# WireLessPhone_Amp.net
KiCad netlist of a schematic drawn in Altium Designer
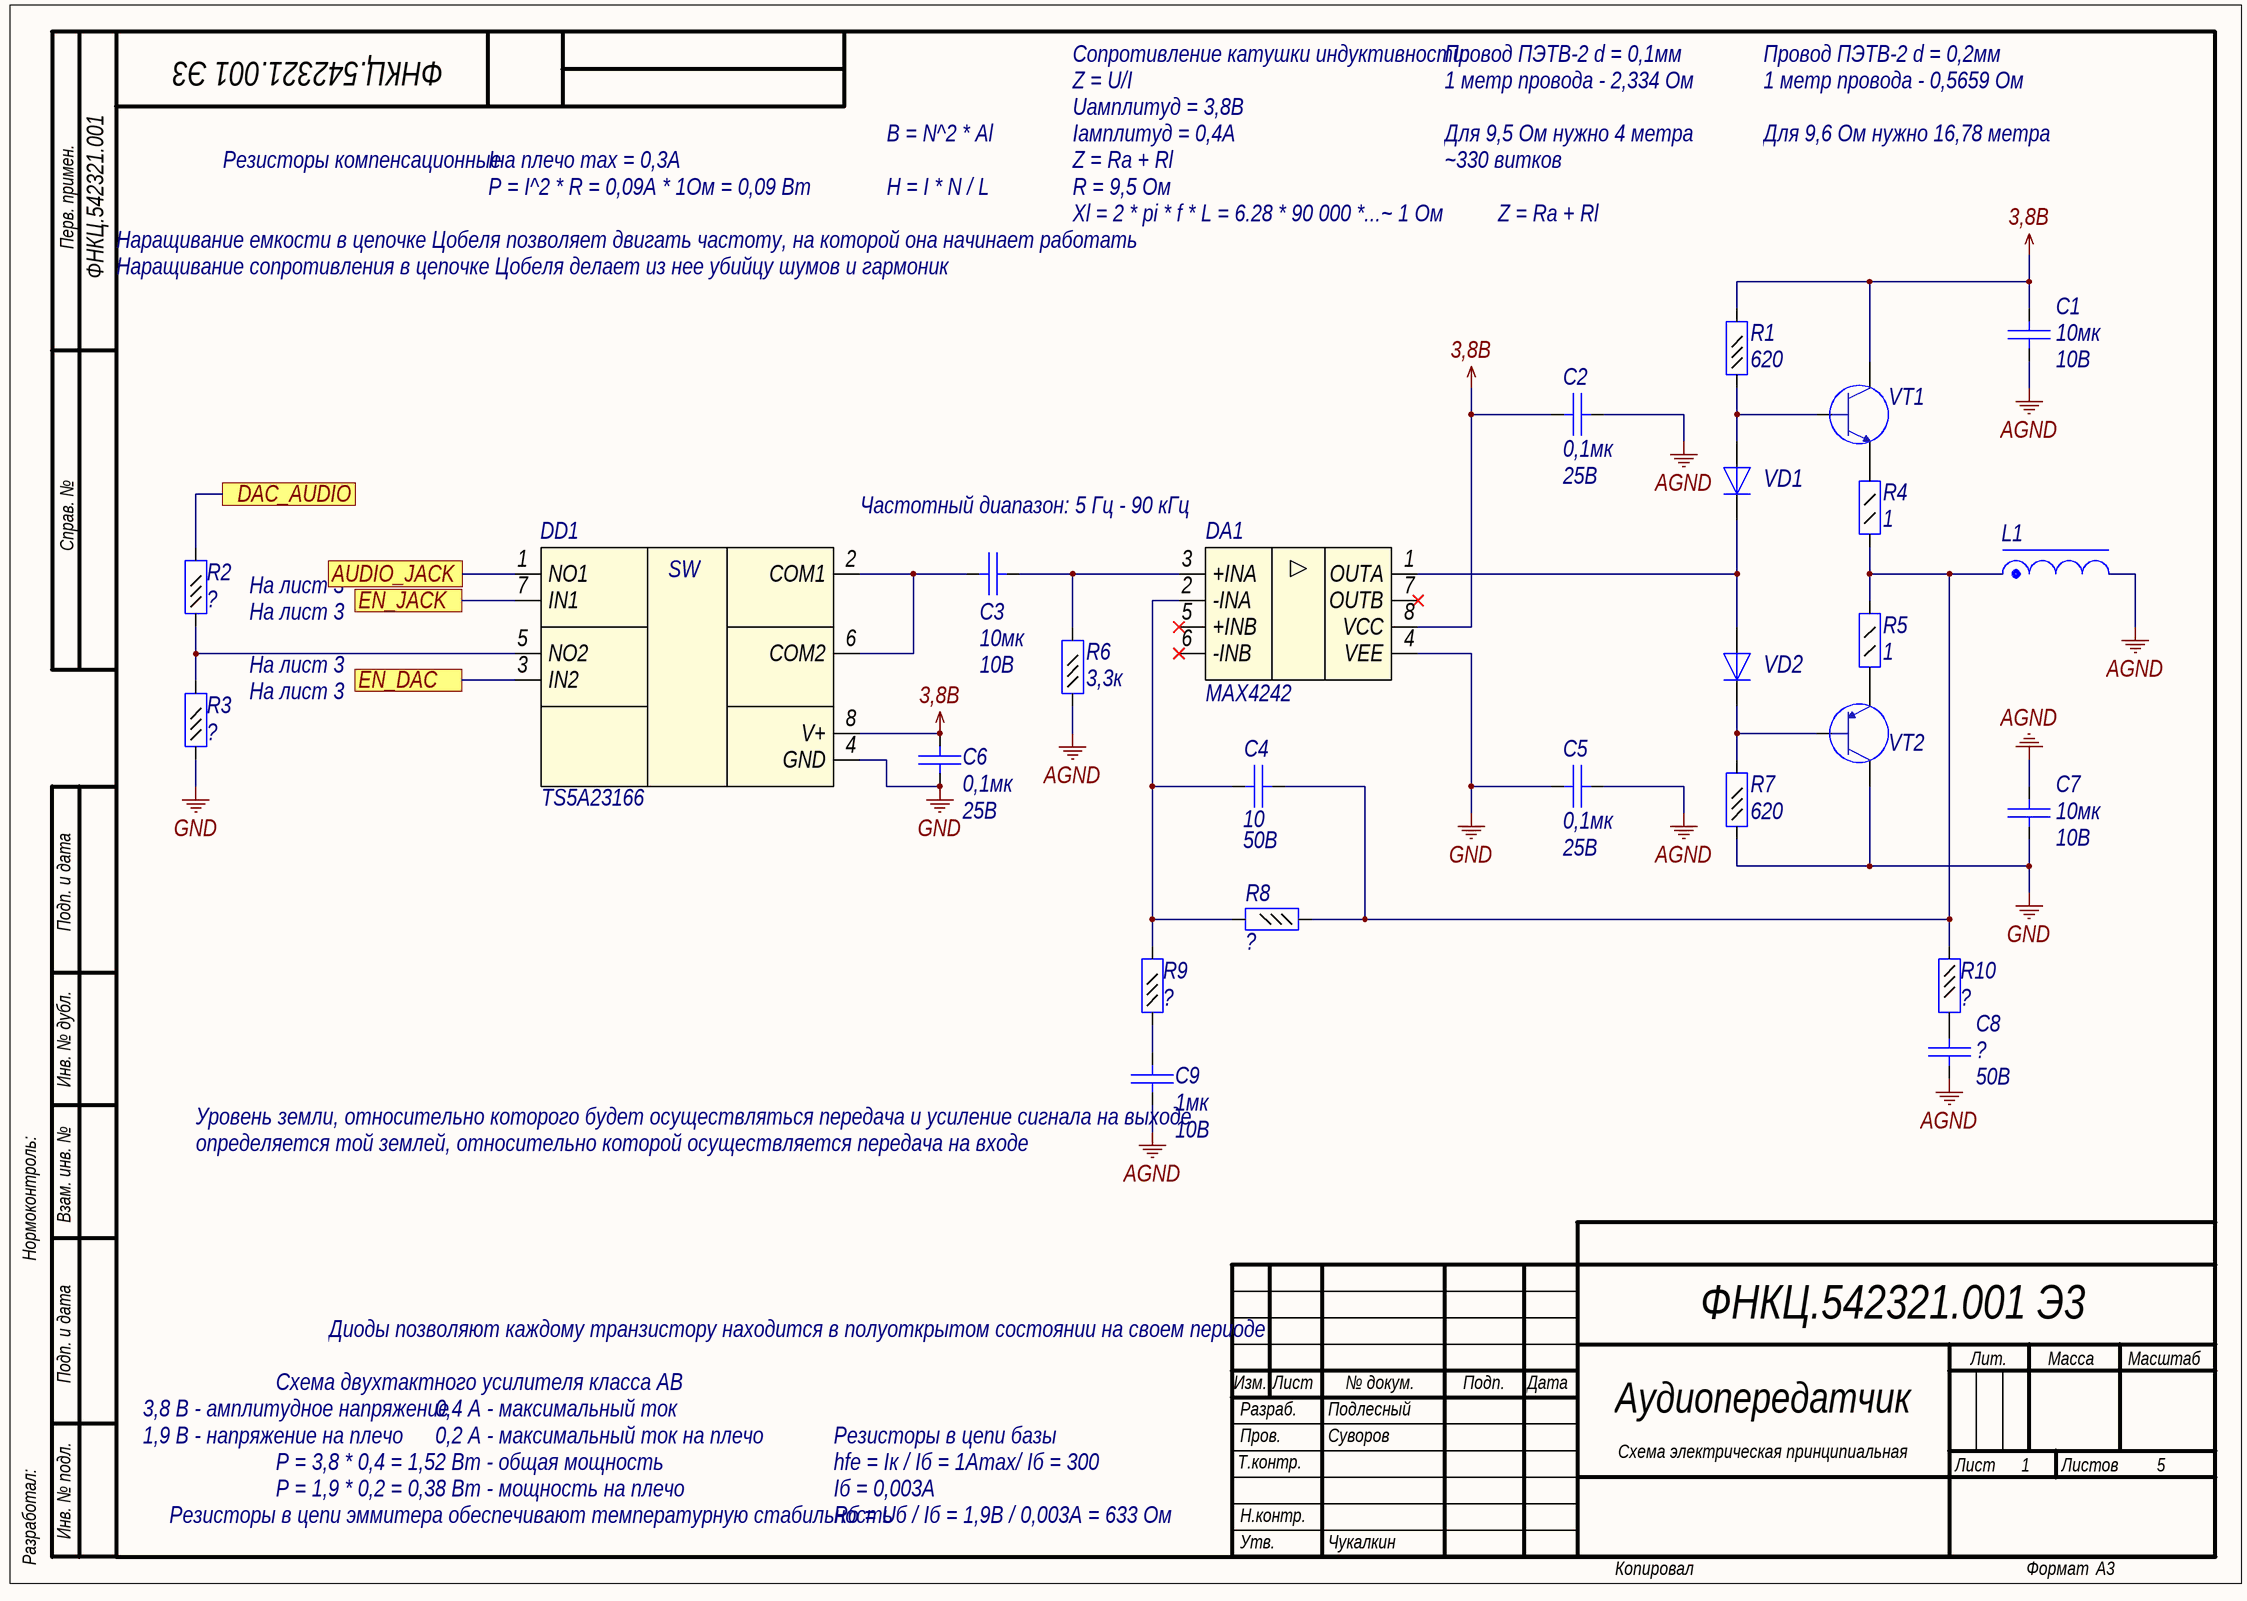
[diagram p0: WireLessPhone_Amp.SchDoc]

(export (version "E")
  (design (tool "Eeschema 10.0.6"))
  (components
    (comp (ref "C1")
      (value "10мк")
      (footprint "C0805")
      (description "Конденсатор")
      (fields
        (field (name "VOLTAGE") "10В")
        (field (name "PART NUMBER") "GRM21BR71A106KE51L")
        (field (name "Comment") "Capacitor")
      )
      (libsource (lib "MOP44") (part "Capacitor"))
    )
    (comp (ref "C2")
      (value "0,1мк")
      (footprint "C0402")
      (description "Конденсатор")
      (fields
        (field (name "VOLTAGE") "25B")
        (field (name "PART NUMBER") "GRM155F51E104Z**")
        (field (name "Comment") "Capacitor")
      )
      (libsource (lib "MOP44") (part "Capacitor"))
    )
    (comp (ref "C3")
      (value "10мк")
      (footprint "C0805")
      (description "Конденсатор")
      (fields
        (field (name "VOLTAGE") "10В")
        (field (name "PART NUMBER") "GRM21BR71A106KE51L")
        (field (name "Comment") "Capacitor")
      )
      (libsource (lib "MOP44") (part "Capacitor"))
    )
    (comp (ref "C4")
      (value "10")
      (footprint "C0402")
      (description "Конденсатор")
      (fields
        (field (name "VOLTAGE") "50B")
        (field (name "PART NUMBER") "GRM1535C1H100J")
        (field (name "Comment") "Capacitor")
      )
      (libsource (lib "MOP44") (part "Capacitor"))
    )
    (comp (ref "C5")
      (value "0,1мк")
      (footprint "C0402")
      (description "Конденсатор")
      (fields
        (field (name "VOLTAGE") "25B")
        (field (name "PART NUMBER") "GRM155F51E104Z**")
        (field (name "Comment") "Capacitor")
      )
      (libsource (lib "MOP44") (part "Capacitor"))
    )
    (comp (ref "C6")
      (value "0,1мк")
      (footprint "C0402")
      (description "Конденсатор")
      (fields
        (field (name "VOLTAGE") "25B")
        (field (name "PART NUMBER") "GRM155F51E104Z**")
        (field (name "Comment") "Capacitor")
      )
      (libsource (lib "MOP44") (part "Capacitor"))
    )
    (comp (ref "C7")
      (value "10мк")
      (footprint "C0805")
      (description "Конденсатор")
      (fields
        (field (name "VOLTAGE") "10В")
        (field (name "PART NUMBER") "GRM21BR71A106KE51L")
        (field (name "Comment") "Capacitor")
      )
      (libsource (lib "MOP44") (part "Capacitor"))
    )
    (comp (ref "C8")
      (value "?")
      (footprint "C0402")
      (description "Конденсатор")
      (fields
        (field (name "VOLTAGE") "50B")
        (field (name "PART NUMBER") "GRM1535C1H100J")
        (field (name "Comment") "Capacitor")
      )
      (libsource (lib "MOP44") (part "Capacitor"))
    )
    (comp (ref "C9")
      (value "1мк")
      (footprint "C0402")
      (description "Конденсатор")
      (fields
        (field (name "VOLTAGE") "10B")
        (field (name "PART NUMBER") "GRM155R61A105K")
        (field (name "Comment") "Capacitor")
      )
      (libsource (lib "MOP44") (part "Capacitor"))
    )
    (comp (ref "DA1")
      (value "MAX4242")
      (footprint "8µMAX")
      (description "МИКРОМОЩНЫЙ Single/Dual/Quad, +1.8V/10µA, SOT23,  Beyond-the-Rails Op Amps")
      (fields (field (name "PART NUMBER") "MAX4242EUA"))
      (libsource (lib "MOP44") (part "MAX4242"))
    )
    (comp (ref "DD1")
      (value "TS5A23166")
      (footprint "US8")
      (description "Dual-SPST Analog Switch")
      (libsource (lib "MOP44") (part "TS5A23166"))
    )
    (comp (ref "L1")
      (value "InductorSerd")
      (footprint "InductorPetlya")
      (description "EMI Suppression Filter")
      (libsource (lib "MOP44") (part "InductorSerd"))
    )
    (comp (ref "R1")
      (value "620")
      (footprint "R0402")
      (description "Резистор")
      (fields (field (name "PART NUMBER") "RC0402FR-07620RL") (field (name "POWER") "0,062Вт"))
      (libsource (lib "MOP44") (part "Resistor_0,062Вт"))
    )
    (comp (ref "R2")
      (value "?")
      (footprint "R0402")
      (description "Резистор")
      (fields (field (name "PART NUMBER") "RC0402FR-072K3") (field (name "POWER") "0,062Вт"))
      (libsource (lib "MOP44") (part "Resistor_0,062Вт"))
    )
    (comp (ref "R3")
      (value "?")
      (footprint "R0402")
      (description "Резистор")
      (fields (field (name "PART NUMBER") "RC0402FR-072K3") (field (name "POWER") "0,062Вт"))
      (libsource (lib "MOP44") (part "Resistor_0,062Вт"))
    )
    (comp (ref "R4")
      (value "1")
      (footprint "R0805")
      (description "Резистор")
      (fields (field (name "PART NUMBER") "RC0805FR-071RL") (field (name "POWER") "0,125Вт"))
      (libsource (lib "MOP44") (part "Resistor_0,125Вт"))
    )
    (comp (ref "R5")
      (value "1")
      (footprint "R0805")
      (description "Резистор")
      (fields (field (name "PART NUMBER") "RC0805FR-071RL") (field (name "POWER") "0,125Вт"))
      (libsource (lib "MOP44") (part "Resistor_0,125Вт"))
    )
    (comp (ref "R6")
      (value "3,3к")
      (footprint "R0402")
      (description "Резистор")
      (fields (field (name "PART NUMBER") "RC0402FR-072K3") (field (name "POWER") "0,062Вт"))
      (libsource (lib "MOP44") (part "Resistor_0,062Вт"))
    )
    (comp (ref "R7")
      (value "620")
      (footprint "R0402")
      (description "Резистор")
      (fields (field (name "PART NUMBER") "RC0402FR-07620RL") (field (name "POWER") "0,062Вт"))
      (libsource (lib "MOP44") (part "Resistor_0,062Вт"))
    )
    (comp (ref "R8")
      (value "?")
      (footprint "R0402")
      (description "Резистор")
      (fields (field (name "PART NUMBER") "RC0402FR-072K3") (field (name "POWER") "0,062Вт"))
      (libsource (lib "") (part "Resistor_0,062Вт_2"))
    )
    (comp (ref "R9")
      (value "?")
      (footprint "R0402")
      (description "Резистор")
      (fields (field (name "PART NUMBER") "RC0402FR-072K3") (field (name "POWER") "0,062Вт"))
      (libsource (lib "MOP44") (part "Resistor_0,062Вт"))
    )
    (comp (ref "R10")
      (value "?")
      (footprint "R0402")
      (description "Резистор")
      (fields (field (name "PART NUMBER") "RC0402FR-072K3") (field (name "POWER") "0,062Вт"))
      (libsource (lib "") (part "Resistor_0,062Вт_1"))
    )
    (comp (ref "VD1")
      (value "Diode")
      (footprint "SOD-323")
      (description "Диод")
      (fields (field (name "PART NUMBER") "BAS321.115"))
      (libsource (lib "MOP44") (part "Diode"))
    )
    (comp (ref "VD2")
      (value "Diode")
      (footprint "SOD-323")
      (description "Диод")
      (fields (field (name "PART NUMBER") "BAS321.115"))
      (libsource (lib "MOP44") (part "Diode"))
    )
    (comp (ref "VT1")
      (value "BJT NPN")
      (footprint "SOT-223")
      (fields (field (name "POWER") "2Вт") (field (name "PART NUMBER") "PBSS4540Z.115"))
      (libsource (lib "MOP44") (part "BJT NPN"))
    )
    (comp (ref "VT2")
      (value "BJT PNP")
      (footprint "SOT-223")
      (fields (field (name "POWER") "2Вт") (field (name "PART NUMBER") "PBSS5540Z.115"))
      (libsource (lib "MOP44") (part "BJT PNP"))
    )
  )
  (nets
    (net (code "1") (name "/AUDIO_JACK") (class "Default")
      (node (ref "DD1") (pin "1") (pinfunction "NO1_1") (pintype "power_in"))
    )
    (net (code "2") (name "/DAC_AUDIO") (class "Default")
      (node (ref "R2") (pin "2") (pinfunction "2_2") (pintype "passive"))
    )
    (net (code "3") (name "/EN_DAC") (class "Default")
      (node (ref "DD1") (pin "3") (pinfunction "IN2_3") (pintype "power_in"))
    )
    (net (code "4") (name "/EN_JACK") (class "Default")
      (node (ref "DD1") (pin "7") (pinfunction "IN1_7") (pintype "power_in"))
    )
    (net (code "5") (name "3,8B") (class "Default")
      (node (ref "C1") (pin "2") (pinfunction "2_2") (pintype "passive"))
      (node (ref "C2") (pin "2") (pinfunction "2_2") (pintype "passive"))
      (node (ref "C6") (pin "1") (pinfunction "1_1") (pintype "passive"))
      (node (ref "DA1") (pin "8") (pinfunction "VCC_8") (pintype "passive"))
      (node (ref "DD1") (pin "8") (pinfunction "V+_8") (pintype "power_in"))
      (node (ref "R1") (pin "2") (pinfunction "2_2") (pintype "passive"))
      (node (ref "VT1") (pin "2") (pinfunction "2_2") (pintype "passive"))
    )
    (net (code "6") (name "AGND") (class "Default")
      (node (ref "C1") (pin "1") (pinfunction "1_1") (pintype "passive"))
      (node (ref "C2") (pin "1") (pinfunction "1_1") (pintype "passive"))
      (node (ref "C5") (pin "1") (pinfunction "1_1") (pintype "passive"))
      (node (ref "C7") (pin "2") (pinfunction "2_2") (pintype "passive"))
      (node (ref "C8") (pin "1") (pinfunction "1_1") (pintype "passive"))
      (node (ref "C9") (pin "1") (pinfunction "1_1") (pintype "passive"))
      (node (ref "L1") (pin "2") (pinfunction "2_2") (pintype "passive"))
      (node (ref "R6") (pin "1") (pinfunction "1_1") (pintype "passive"))
    )
    (net (code "7") (name "GND") (class "Default")
      (node (ref "C5") (pin "2") (pinfunction "2_2") (pintype "passive"))
      (node (ref "C6") (pin "2") (pinfunction "2_2") (pintype "passive"))
      (node (ref "C7") (pin "1") (pinfunction "1_1") (pintype "passive"))
      (node (ref "DA1") (pin "4") (pinfunction "VEE_4") (pintype "passive"))
      (node (ref "DD1") (pin "4") (pinfunction "GND_4") (pintype "power_in"))
      (node (ref "R3") (pin "1") (pinfunction "1_1") (pintype "passive"))
      (node (ref "R7") (pin "1") (pinfunction "1_1") (pintype "passive"))
      (node (ref "VT2") (pin "2") (pinfunction "2_2") (pintype "passive"))
    )
    (net (code "8") (name "Net-(C4-Pad2)") (class "Default")
      (node (ref "C4") (pin "2") (pinfunction "2_2") (pintype "passive"))
      (node (ref "L1") (pin "1") (pinfunction "1_1") (pintype "passive"))
      (node (ref "R10") (pin "1") (pinfunction "1_1") (pintype "passive"))
      (node (ref "R4") (pin "1") (pinfunction "1_1") (pintype "passive"))
      (node (ref "R5") (pin "2") (pinfunction "2_2") (pintype "passive"))
      (node (ref "R8") (pin "1") (pinfunction "1_1") (pintype "passive"))
    )
    (net (code "9") (name "Net-(C8-Pad2)") (class "Default")
      (node (ref "C8") (pin "2") (pinfunction "2_2") (pintype "passive"))
      (node (ref "R10") (pin "2") (pinfunction "2_2") (pintype "passive"))
    )
    (net (code "10") (name "Net-(C9-Pad2)") (class "Default")
      (node (ref "C9") (pin "2") (pinfunction "2_2") (pintype "passive"))
      (node (ref "R9") (pin "1") (pinfunction "1_1") (pintype "passive"))
    )
    (net (code "11") (name "Net-(DA1-+INA)") (class "Default")
      (node (ref "C3") (pin "2") (pinfunction "2_2") (pintype "passive"))
      (node (ref "DA1") (pin "3") (pinfunction "+INA_3") (pintype "passive"))
      (node (ref "R6") (pin "2") (pinfunction "2_2") (pintype "passive"))
    )
    (net (code "12") (name "Net-(DA1--INA)") (class "Default")
      (node (ref "C4") (pin "1") (pinfunction "1_1") (pintype "passive"))
      (node (ref "DA1") (pin "2") (pinfunction "-INA_2") (pintype "passive"))
      (node (ref "R8") (pin "2") (pinfunction "2_2") (pintype "passive"))
      (node (ref "R9") (pin "2") (pinfunction "2_2") (pintype "passive"))
    )
    (net (code "13") (name "Net-(DA1-OUTA)") (class "Default")
      (node (ref "DA1") (pin "1") (pinfunction "OUTA_1") (pintype "passive"))
      (node (ref "VD1") (pin "1") (pinfunction "K_1") (pintype "passive"))
      (node (ref "VD2") (pin "2") (pinfunction "A_2") (pintype "passive"))
    )
    (net (code "14") (name "Net-(DD1-COM1)") (class "Default")
      (node (ref "C3") (pin "1") (pinfunction "1_1") (pintype "passive"))
      (node (ref "DD1") (pin "2") (pinfunction "COM1_2") (pintype "power_in"))
      (node (ref "DD1") (pin "6") (pinfunction "COM2_6") (pintype "power_in"))
    )
    (net (code "15") (name "Net-(DD1-NO2)") (class "Default")
      (node (ref "DD1") (pin "5") (pinfunction "NO2_5") (pintype "power_in"))
      (node (ref "R2") (pin "1") (pinfunction "1_1") (pintype "passive"))
      (node (ref "R3") (pin "2") (pinfunction "2_2") (pintype "passive"))
    )
    (net (code "16") (name "Net-(R4-Pad2)") (class "Default")
      (node (ref "R4") (pin "2") (pinfunction "2_2") (pintype "passive"))
      (node (ref "VT1") (pin "3") (pinfunction "3_3") (pintype "passive"))
    )
    (net (code "17") (name "Net-(R5-Pad1)") (class "Default")
      (node (ref "R5") (pin "1") (pinfunction "1_1") (pintype "passive"))
      (node (ref "VT2") (pin "3") (pinfunction "3_3") (pintype "passive"))
    )
    (net (code "18") (name "Net-(VD1-A)") (class "Default")
      (node (ref "R1") (pin "1") (pinfunction "1_1") (pintype "passive"))
      (node (ref "VD1") (pin "2") (pinfunction "A_2") (pintype "passive"))
      (node (ref "VT1") (pin "1") (pinfunction "1_1") (pintype "passive"))
    )
    (net (code "19") (name "Net-(VD2-K)") (class "Default")
      (node (ref "R7") (pin "2") (pinfunction "2_2") (pintype "passive"))
      (node (ref "VD2") (pin "1") (pinfunction "K_1") (pintype "passive"))
      (node (ref "VT2") (pin "1") (pinfunction "1_1") (pintype "passive"))
    )
    (net (code "20") (name "unconnected-(DA1-+INB-Pad5)") (class "Default")
      (node (ref "DA1") (pin "5") (pinfunction "+INB_5") (pintype "passive+no_connect"))
    )
    (net (code "21") (name "unconnected-(DA1--INB-Pad6)") (class "Default")
      (node (ref "DA1") (pin "6") (pinfunction "-INB_6") (pintype "passive+no_connect"))
    )
    (net (code "22") (name "unconnected-(DA1-OUTB-Pad7)") (class "Default")
      (node (ref "DA1") (pin "7") (pinfunction "OUTB_7") (pintype "passive+no_connect"))
    )
  )
)
